# lazurite_rev3_3.net
KiCad netlist of a schematic drawn in EAGLE
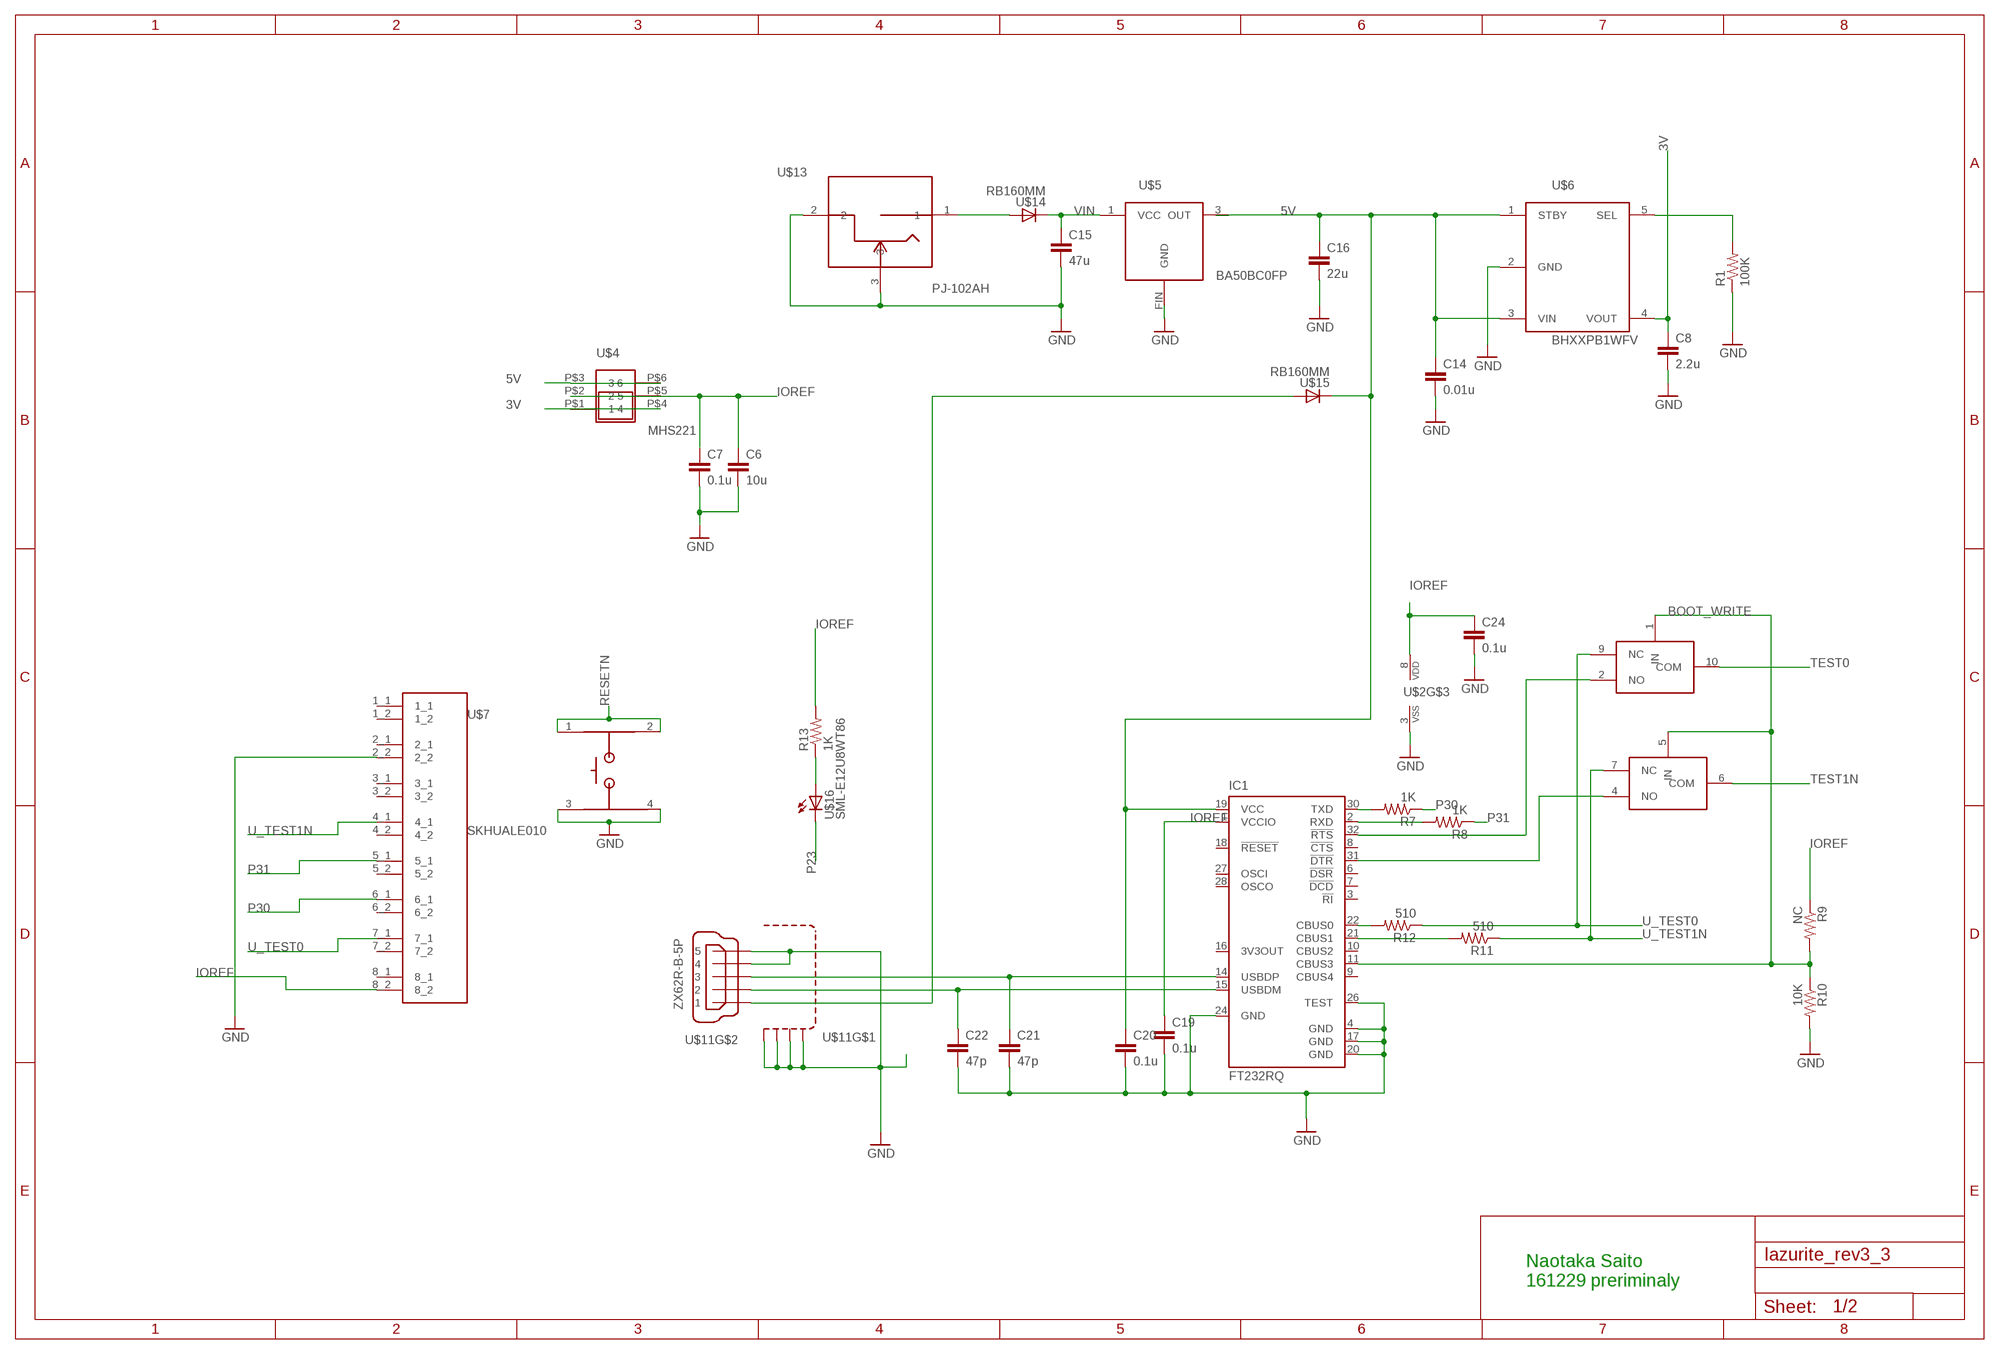
[diagram p0: schematic, sheet 1]
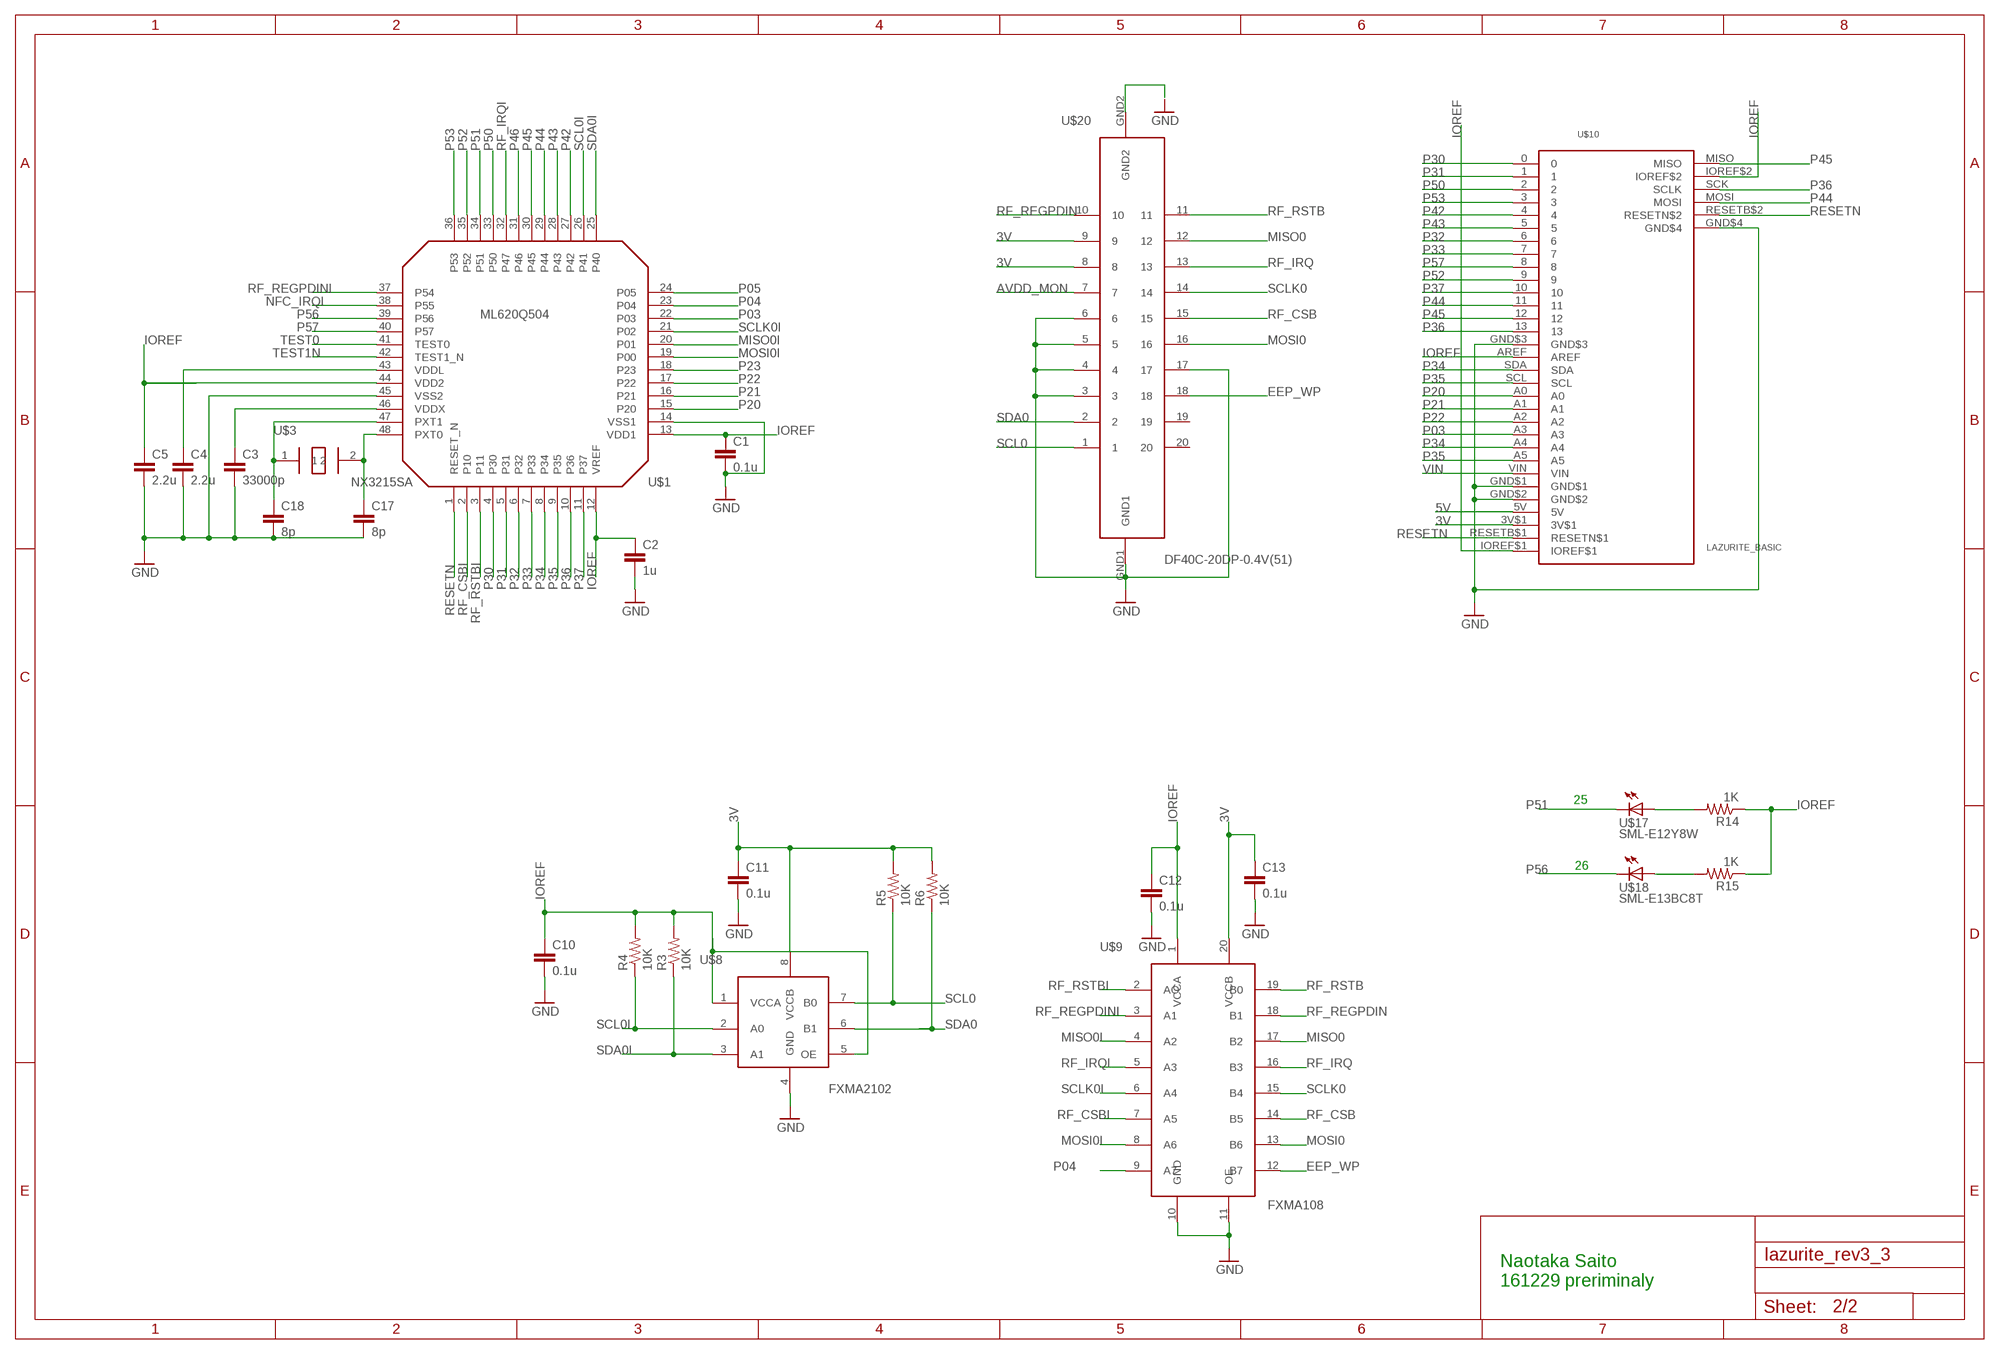
[diagram p1: schematic, sheet 2]

(export (version "E")
  (design (tool "Eeschema 10.0.6"))
  (components
    (comp (ref "C6")
      (value "10u")
      (footprint "eagle-import:C0402")
      (libsource (lib "eagle-import") (part "C-EUC0402"))
    )
    (comp (ref "C7")
      (value "0.1u")
      (footprint "eagle-import:C0402")
      (libsource (lib "eagle-import") (part "C-EUC0402"))
    )
    (comp (ref "C8")
      (value "2.2u")
      (footprint "eagle-import:C0402")
      (libsource (lib "eagle-import") (part "C-EUC0402"))
    )
    (comp (ref "C14")
      (value "0.01u")
      (footprint "eagle-import:C0402")
      (libsource (lib "eagle-import") (part "C-EUC0402"))
    )
    (comp (ref "C15")
      (value "47u")
      (footprint "eagle-import:C1210")
      (libsource (lib "eagle-import") (part "C-EUC1210"))
    )
    (comp (ref "C16")
      (value "22u")
      (footprint "eagle-import:C1206")
      (libsource (lib "eagle-import") (part "C-EUC1206"))
    )
    (comp (ref "C19")
      (value "0.1u")
      (footprint "eagle-import:C0402")
      (libsource (lib "eagle-import") (part "C-EUC0402"))
    )
    (comp (ref "C20")
      (value "0.1u")
      (footprint "eagle-import:C0402")
      (libsource (lib "eagle-import") (part "C-EUC0402"))
    )
    (comp (ref "C21")
      (value "47p")
      (footprint "eagle-import:C0402")
      (libsource (lib "eagle-import") (part "C-EUC0402"))
    )
    (comp (ref "C22")
      (value "47p")
      (footprint "eagle-import:C0402")
      (libsource (lib "eagle-import") (part "C-EUC0402"))
    )
    (comp (ref "C24")
      (value "0.1u")
      (footprint "eagle-import:C0402")
      (libsource (lib "eagle-import") (part "C-EUC0402"))
    )
    (comp (ref "IC1")
      (value "FT232RQ")
      (footprint "eagle-import:QFN32")
      (libsource (lib "eagle-import") (part "FT232RQ"))
    )
    (comp (ref "R1")
      (value "100K")
      (footprint "eagle-import:R0402")
      (libsource (lib "eagle-import") (part "R-US_R0402"))
    )
    (comp (ref "R7")
      (value "1K")
      (footprint "eagle-import:R0402")
      (libsource (lib "eagle-import") (part "R-US_R0402"))
    )
    (comp (ref "R8")
      (value "1K")
      (footprint "eagle-import:R0402")
      (libsource (lib "eagle-import") (part "R-US_R0402"))
    )
    (comp (ref "R9")
      (value "NC")
      (footprint "eagle-import:R0402")
      (libsource (lib "eagle-import") (part "R-US_R0402"))
    )
    (comp (ref "R10")
      (value "10K")
      (footprint "eagle-import:R0402")
      (libsource (lib "eagle-import") (part "R-US_R0402"))
    )
    (comp (ref "R11")
      (value "510")
      (footprint "eagle-import:R0402")
      (libsource (lib "eagle-import") (part "R-US_R0402"))
    )
    (comp (ref "R12")
      (value "510")
      (footprint "eagle-import:R0402")
      (libsource (lib "eagle-import") (part "R-US_R0402"))
    )
    (comp (ref "R13")
      (value "1K")
      (footprint "eagle-import:R0402")
      (libsource (lib "eagle-import") (part "R-US_R0402"))
    )
    (comp (ref "U$2")
      (value "TI-TS5A23159")
      (footprint "eagle-import:UQFN10")
      (libsource (lib "eagle-import") (part "TI-TS5A23159"))
    )
    (comp (ref "U$4")
      (value "MHS221")
      (footprint "eagle-import:MHS221")
      (libsource (lib "eagle-import") (part "MHS221"))
    )
    (comp (ref "U$5")
      (value "BA50BC0FP")
      (footprint "eagle-import:TO252-3")
      (libsource (lib "eagle-import") (part "BA50BC0FP"))
    )
    (comp (ref "U$6")
      (value "BHXXPB1WFV")
      (footprint "eagle-import:HVSOF5")
      (libsource (lib "eagle-import") (part "BHXXPB1WFV"))
    )
    (comp (ref "U$7")
      (value "SKHUALE010")
      (footprint "eagle-import:SKHUALE010")
      (libsource (lib "eagle-import") (part "SKHUALE010"))
    )
    (comp (ref "U$11")
      (value "ZX62R-B-5P")
      (footprint "eagle-import:ZX62R-B-5P")
      (libsource (lib "eagle-import") (part "MICRO-USB-SHIELD-ZX62R-B-5P"))
    )
    (comp (ref "U$12")
      (value "XB-1-X")
      (footprint "eagle-import:XB-1-X")
      (libsource (lib "eagle-import") (part "XB-1-X"))
    )
    (comp (ref "U$13")
      (value "PJ-102AH")
      (footprint "eagle-import:PJ-102H")
      (libsource (lib "eagle-import") (part "PJ-102AH"))
    )
    (comp (ref "U$14")
      (value "RB160MM")
      (footprint "eagle-import:RB160MM-30")
      (libsource (lib "eagle-import") (part "RB160MM"))
    )
    (comp (ref "U$15")
      (value "RB160MM")
      (footprint "eagle-import:RB160MM-30")
      (libsource (lib "eagle-import") (part "RB160MM"))
    )
    (comp (ref "U$16")
      (value "SML-E12U8WT86")
      (footprint "eagle-import:SML-E1X")
      (libsource (lib "eagle-import") (part "SML-E1X"))
    )
    (comp (ref "C1")
      (value "0.1u")
      (footprint "eagle-import:C0402")
      (libsource (lib "eagle-import") (part "C-EUC0402"))
    )
    (comp (ref "C2")
      (value "1u")
      (footprint "eagle-import:C0402")
      (libsource (lib "eagle-import") (part "C-EUC0402"))
    )
    (comp (ref "C3")
      (value "33000p")
      (footprint "eagle-import:C0402")
      (libsource (lib "eagle-import") (part "C-EUC0402"))
    )
    (comp (ref "C4")
      (value "2.2u")
      (footprint "eagle-import:C0402")
      (libsource (lib "eagle-import") (part "C-EUC0402"))
    )
    (comp (ref "C5")
      (value "2.2u")
      (footprint "eagle-import:C0402")
      (libsource (lib "eagle-import") (part "C-EUC0402"))
    )
    (comp (ref "C10")
      (value "0.1u")
      (footprint "eagle-import:C0402")
      (libsource (lib "eagle-import") (part "C-EUC0402"))
    )
    (comp (ref "C11")
      (value "0.1u")
      (footprint "eagle-import:C0402")
      (libsource (lib "eagle-import") (part "C-EUC0402"))
    )
    (comp (ref "C12")
      (value "0.1u")
      (footprint "eagle-import:C0402")
      (libsource (lib "eagle-import") (part "C-EUC0402"))
    )
    (comp (ref "C13")
      (value "0.1u")
      (footprint "eagle-import:C0402")
      (libsource (lib "eagle-import") (part "C-EUC0402"))
    )
    (comp (ref "C17")
      (value "8p")
      (footprint "eagle-import:C0402")
      (libsource (lib "eagle-import") (part "C-EUC0402"))
    )
    (comp (ref "C18")
      (value "8p")
      (footprint "eagle-import:C0402")
      (libsource (lib "eagle-import") (part "C-EUC0402"))
    )
    (comp (ref "R3")
      (value "10K")
      (footprint "eagle-import:R0402")
      (libsource (lib "eagle-import") (part "R-US_R0402"))
    )
    (comp (ref "R4")
      (value "10K")
      (footprint "eagle-import:R0402")
      (libsource (lib "eagle-import") (part "R-US_R0402"))
    )
    (comp (ref "R5")
      (value "10K")
      (footprint "eagle-import:R0402")
      (libsource (lib "eagle-import") (part "R-US_R0402"))
    )
    (comp (ref "R6")
      (value "10K")
      (footprint "eagle-import:R0402")
      (libsource (lib "eagle-import") (part "R-US_R0402"))
    )
    (comp (ref "R14")
      (value "1K")
      (footprint "eagle-import:R0402")
      (libsource (lib "eagle-import") (part "R-US_R0402"))
    )
    (comp (ref "R15")
      (value "1K")
      (footprint "eagle-import:R0402")
      (libsource (lib "eagle-import") (part "R-US_R0402"))
    )
    (comp (ref "U$1")
      (value "ML620Q504")
      (footprint "eagle-import:ML620Q504")
      (libsource (lib "eagle-import") (part "ML620Q504"))
    )
    (comp (ref "U$3")
      (value "NX3215SA")
      (footprint "eagle-import:NX3215SA-32,768K-SFD-MUA-14")
      (libsource (lib "eagle-import") (part "NX3215SA"))
    )
    (comp (ref "U$8")
      (value "FXMA2102")
      (footprint "eagle-import:MICROPACK")
      (libsource (lib "eagle-import") (part "FXMA2102"))
    )
    (comp (ref "U$9")
      (value "FXMA108")
      (footprint "eagle-import:FXMA108")
      (libsource (lib "eagle-import") (part "FXMA108"))
    )
    (comp (ref "U$10")
      (value "LAZURITE_BASIC")
      (footprint "eagle-import:LAZURITE_BASIC")
      (libsource (lib "eagle-import") (part "LAZURITE_BASIC"))
    )
    (comp (ref "U$17")
      (value "SML-E12Y8W")
      (footprint "eagle-import:SML-E1X")
      (libsource (lib "eagle-import") (part "SML-E1X"))
    )
    (comp (ref "U$18")
      (value "SML-E13BC8T")
      (footprint "eagle-import:SML-E1X")
      (libsource (lib "eagle-import") (part "SML-E1X"))
    )
    (comp (ref "U$20")
      (value "DF40C-20DP-0.4V(51)")
      (footprint "eagle-import:BP3596A")
      (libsource (lib "eagle-import") (part "BP3596A"))
    )
  )
  (nets
    (net (code "1") (name "3V") (class "Default")
      (node (ref "C11") (pin "1") (pinfunction "1_1") (pintype "passive"))
      (node (ref "C13") (pin "1") (pinfunction "1_1") (pintype "passive"))
      (node (ref "C8") (pin "1") (pinfunction "1_1") (pintype "passive"))
      (node (ref "R5") (pin "2") (pinfunction "2_2") (pintype "passive"))
      (node (ref "R6") (pin "2") (pinfunction "2_2") (pintype "passive"))
      (node (ref "U$10") (pin "3V$1") (pinfunction "3V$1_3V$1") (pintype "power_in"))
      (node (ref "U$20") (pin "8") (pinfunction "8_8") (pintype "bidirectional"))
      (node (ref "U$20") (pin "9") (pinfunction "9_9") (pintype "bidirectional"))
      (node (ref "U$4") (pin "P$1") (pinfunction "1_P$1") (pintype "bidirectional"))
      (node (ref "U$4") (pin "P$4") (pinfunction "4_P$4") (pintype "bidirectional"))
      (node (ref "U$6") (pin "4") (pinfunction "VOUT_4") (pintype "bidirectional"))
      (node (ref "U$8") (pin "8") (pinfunction "VCCB_8") (pintype "bidirectional"))
      (node (ref "U$9") (pin "20") (pinfunction "VCCB_20") (pintype "bidirectional"))
    )
    (net (code "2") (name "5V") (class "Default")
      (node (ref "C14") (pin "1") (pinfunction "1_1") (pintype "passive"))
      (node (ref "C16") (pin "1") (pinfunction "1_1") (pintype "passive"))
      (node (ref "C20") (pin "1") (pinfunction "1_1") (pintype "passive"))
      (node (ref "IC1") (pin "19") (pinfunction "VCC_19") (pintype "power_in"))
      (node (ref "U$10") (pin "5V") (pinfunction "5V_5V") (pintype "power_in"))
      (node (ref "U$15") (pin "C") (pinfunction "C_C") (pintype "passive"))
      (node (ref "U$4") (pin "P$3") (pinfunction "3_P$3") (pintype "bidirectional"))
      (node (ref "U$4") (pin "P$6") (pinfunction "6_P$6") (pintype "bidirectional"))
      (node (ref "U$5") (pin "3") (pinfunction "OUT_3") (pintype "bidirectional"))
      (node (ref "U$6") (pin "1") (pinfunction "STBY_1") (pintype "bidirectional"))
      (node (ref "U$6") (pin "3") (pinfunction "VIN_3") (pintype "bidirectional"))
    )
    (net (code "3") (name "AVDD_MON") (class "Default")
      (node (ref "U$20") (pin "7") (pinfunction "7_7") (pintype "bidirectional"))
    )
    (net (code "4") (name "BOOT_WRITE") (class "Default")
      (node (ref "IC1") (pin "11") (pinfunction "CBUS3_11") (pintype "bidirectional"))
      (node (ref "R10") (pin "1") (pinfunction "1_1") (pintype "passive"))
      (node (ref "R9") (pin "2") (pinfunction "2_2") (pintype "passive"))
      (node (ref "U$2") (pin "1") (pinfunction "IN_1") (pintype "bidirectional"))
      (node (ref "U$2") (pin "5") (pinfunction "IN_5") (pintype "bidirectional"))
    )
    (net (code "5") (name "EEP_WP") (class "Default")
      (node (ref "U$20") (pin "18") (pinfunction "18_18") (pintype "bidirectional"))
      (node (ref "U$9") (pin "12") (pinfunction "B7_12") (pintype "bidirectional"))
    )
    (net (code "6") (name "GND") (class "Default")
      (node (ref "C1") (pin "2") (pinfunction "2_2") (pintype "passive"))
      (node (ref "C10") (pin "2") (pinfunction "2_2") (pintype "passive"))
      (node (ref "C11") (pin "2") (pinfunction "2_2") (pintype "passive"))
      (node (ref "C12") (pin "2") (pinfunction "2_2") (pintype "passive"))
      (node (ref "C13") (pin "2") (pinfunction "2_2") (pintype "passive"))
      (node (ref "C14") (pin "2") (pinfunction "2_2") (pintype "passive"))
      (node (ref "C15") (pin "2") (pinfunction "2_2") (pintype "passive"))
      (node (ref "C16") (pin "2") (pinfunction "2_2") (pintype "passive"))
      (node (ref "C17") (pin "2") (pinfunction "2_2") (pintype "passive"))
      (node (ref "C18") (pin "2") (pinfunction "2_2") (pintype "passive"))
      (node (ref "C19") (pin "2") (pinfunction "2_2") (pintype "passive"))
      (node (ref "C2") (pin "2") (pinfunction "2_2") (pintype "passive"))
      (node (ref "C20") (pin "2") (pinfunction "2_2") (pintype "passive"))
      (node (ref "C21") (pin "2") (pinfunction "2_2") (pintype "passive"))
      (node (ref "C22") (pin "2") (pinfunction "2_2") (pintype "passive"))
      (node (ref "C24") (pin "2") (pinfunction "2_2") (pintype "passive"))
      (node (ref "C3") (pin "2") (pinfunction "2_2") (pintype "passive"))
      (node (ref "C4") (pin "2") (pinfunction "2_2") (pintype "passive"))
      (node (ref "C5") (pin "2") (pinfunction "2_2") (pintype "passive"))
      (node (ref "C6") (pin "2") (pinfunction "2_2") (pintype "passive"))
      (node (ref "C7") (pin "2") (pinfunction "2_2") (pintype "passive"))
      (node (ref "C8") (pin "2") (pinfunction "2_2") (pintype "passive"))
      (node (ref "IC1") (pin "17") (pinfunction "GND_17") (pintype "power_in"))
      (node (ref "IC1") (pin "20") (pinfunction "GND_20") (pintype "power_in"))
      (node (ref "IC1") (pin "24") (pinfunction "GND_24") (pintype "power_in"))
      (node (ref "IC1") (pin "26") (pinfunction "TEST_26") (pintype "input"))
      (node (ref "IC1") (pin "4") (pinfunction "GND_4") (pintype "power_in"))
      (node (ref "R1") (pin "1") (pinfunction "1_1") (pintype "passive"))
      (node (ref "R10") (pin "2") (pinfunction "2_2") (pintype "passive"))
      (node (ref "U$1") (pin "14") (pinfunction "VSS1_14") (pintype "bidirectional"))
      (node (ref "U$1") (pin "45") (pinfunction "VSS2_45") (pintype "bidirectional"))
      (node (ref "U$10") (pin "GND$1") (pinfunction "GND$1_GND$1") (pintype "power_in"))
      (node (ref "U$10") (pin "GND$2") (pinfunction "GND$2_GND$2") (pintype "power_in"))
      (node (ref "U$10") (pin "GND$3") (pinfunction "GND$3_GND$3") (pintype "power_in"))
      (node (ref "U$10") (pin "GND$4") (pinfunction "GND$4_GND$4") (pintype "power_in"))
      (node (ref "U$11") (pin "4") (pinfunction "4_4") (pintype "input"))
      (node (ref "U$11") (pin "5") (pinfunction "5_5") (pintype "input"))
      (node (ref "U$11") (pin "M1") (pinfunction "S1_M1") (pintype "passive"))
      (node (ref "U$11") (pin "M2") (pinfunction "S2_M2") (pintype "passive"))
      (node (ref "U$11") (pin "M3") (pinfunction "S3_M3") (pintype "passive"))
      (node (ref "U$11") (pin "M4") (pinfunction "S4_M4") (pintype "passive"))
      (node (ref "U$12") (pin "2_2") (pinfunction "2_2_2_2") (pintype "bidirectional"))
      (node (ref "U$13") (pin "2") (pinfunction "2_2") (pintype "bidirectional"))
      (node (ref "U$13") (pin "3") (pinfunction "3_3") (pintype "bidirectional"))
      (node (ref "U$2") (pin "3") (pinfunction "VSS_3") (pintype "power_in"))
      (node (ref "U$20") (pin "17") (pinfunction "17_17") (pintype "bidirectional"))
      (node (ref "U$20") (pin "3") (pinfunction "3_3") (pintype "bidirectional"))
      (node (ref "U$20") (pin "4") (pinfunction "4_4") (pintype "bidirectional"))
      (node (ref "U$20") (pin "5") (pinfunction "5_5") (pintype "bidirectional"))
      (node (ref "U$20") (pin "6") (pinfunction "6_6") (pintype "bidirectional"))
      (node (ref "U$20") (pin "GND1") (pinfunction "GND1_GND1") (pintype "bidirectional"))
      (node (ref "U$5") (pin "FIN") (pinfunction "GND_FIN") (pintype "bidirectional"))
      (node (ref "U$6") (pin "2") (pinfunction "GND_2") (pintype "bidirectional"))
      (node (ref "U$7") (pin "3") (pinfunction "3_3") (pintype "bidirectional"))
      (node (ref "U$7") (pin "4") (pinfunction "4_4") (pintype "bidirectional"))
      (node (ref "U$8") (pin "4") (pinfunction "GND_4") (pintype "bidirectional"))
      (node (ref "U$9") (pin "10") (pinfunction "GND_10") (pintype "bidirectional"))
      (node (ref "U$9") (pin "11") (pinfunction "OE_11") (pintype "bidirectional"))
    )
    (net (code "7") (name "IOREF") (class "Default")
      (node (ref "C1") (pin "1") (pinfunction "1_1") (pintype "passive"))
      (node (ref "C10") (pin "1") (pinfunction "1_1") (pintype "passive"))
      (node (ref "C12") (pin "1") (pinfunction "1_1") (pintype "passive"))
      (node (ref "C19") (pin "1") (pinfunction "1_1") (pintype "passive"))
      (node (ref "C2") (pin "1") (pinfunction "1_1") (pintype "passive"))
      (node (ref "C24") (pin "1") (pinfunction "1_1") (pintype "passive"))
      (node (ref "C5") (pin "1") (pinfunction "1_1") (pintype "passive"))
      (node (ref "C6") (pin "1") (pinfunction "1_1") (pintype "passive"))
      (node (ref "C7") (pin "1") (pinfunction "1_1") (pintype "passive"))
      (node (ref "IC1") (pin "1") (pinfunction "VCCIO_1") (pintype "power_in"))
      (node (ref "R13") (pin "2") (pinfunction "2_2") (pintype "passive"))
      (node (ref "R14") (pin "1") (pinfunction "1_1") (pintype "passive"))
      (node (ref "R15") (pin "1") (pinfunction "1_1") (pintype "passive"))
      (node (ref "R3") (pin "2") (pinfunction "2_2") (pintype "passive"))
      (node (ref "R4") (pin "2") (pinfunction "2_2") (pintype "passive"))
      (node (ref "R9") (pin "1") (pinfunction "1_1") (pintype "passive"))
      (node (ref "U$1") (pin "12") (pinfunction "VREF_12") (pintype "bidirectional"))
      (node (ref "U$1") (pin "13") (pinfunction "VDD1_13") (pintype "bidirectional"))
      (node (ref "U$1") (pin "44") (pinfunction "VDD2_44") (pintype "bidirectional"))
      (node (ref "U$10") (pin "AREF") (pinfunction "AREF_AREF") (pintype "power_in"))
      (node (ref "U$10") (pin "IOREF$1") (pinfunction "IOREF$1_IOREF$1") (pintype "bidirectional"))
      (node (ref "U$10") (pin "IOREF$2") (pinfunction "IOREF$2_IOREF$2") (pintype "power_in"))
      (node (ref "U$12") (pin "8_2") (pinfunction "8_2_8_2") (pintype "bidirectional"))
      (node (ref "U$2") (pin "8") (pinfunction "VDD_8") (pintype "power_in"))
      (node (ref "U$4") (pin "P$2") (pinfunction "2_P$2") (pintype "bidirectional"))
      (node (ref "U$4") (pin "P$5") (pinfunction "5_P$5") (pintype "bidirectional"))
      (node (ref "U$8") (pin "1") (pinfunction "VCCA_1") (pintype "bidirectional"))
      (node (ref "U$8") (pin "5") (pinfunction "OE_5") (pintype "bidirectional"))
      (node (ref "U$9") (pin "1") (pinfunction "VCCA_1") (pintype "bidirectional"))
    )
    (net (code "8") (name "MISO0") (class "Default")
      (node (ref "U$20") (pin "12") (pinfunction "12_12") (pintype "bidirectional"))
      (node (ref "U$9") (pin "17") (pinfunction "B2_17") (pintype "bidirectional"))
    )
    (net (code "9") (name "MISO0I") (class "Default")
      (node (ref "U$1") (pin "20") (pinfunction "P01_20") (pintype "bidirectional"))
      (node (ref "U$9") (pin "4") (pinfunction "A2_4") (pintype "bidirectional"))
    )
    (net (code "10") (name "MOSI0") (class "Default")
      (node (ref "U$20") (pin "16") (pinfunction "16_16") (pintype "bidirectional"))
      (node (ref "U$9") (pin "13") (pinfunction "B6_13") (pintype "bidirectional"))
    )
    (net (code "11") (name "MOSI0I") (class "Default")
      (node (ref "U$1") (pin "19") (pinfunction "P00_19") (pintype "bidirectional"))
      (node (ref "U$9") (pin "8") (pinfunction "A6_8") (pintype "bidirectional"))
    )
    (net (code "12") (name "NFC_IRQI") (class "Default")
      (node (ref "U$1") (pin "38") (pinfunction "P55_38") (pintype "bidirectional"))
    )
    (net (code "13") (name "Net-(IC1-CBUS0)") (class "Default")
      (node (ref "IC1") (pin "22") (pinfunction "CBUS0_22") (pintype "bidirectional"))
      (node (ref "R12") (pin "2") (pinfunction "2_2") (pintype "passive"))
    )
    (net (code "14") (name "Net-(IC1-CBUS1)") (class "Default")
      (node (ref "IC1") (pin "21") (pinfunction "CBUS1_21") (pintype "bidirectional"))
      (node (ref "R11") (pin "2") (pinfunction "2_2") (pintype "passive"))
    )
    (net (code "15") (name "Net-(IC1-RXD)") (class "Default")
      (node (ref "IC1") (pin "2") (pinfunction "RXD_2") (pintype "input"))
      (node (ref "R8") (pin "2") (pinfunction "2_2") (pintype "passive"))
    )
    (net (code "16") (name "Net-(IC1-TXD)") (class "Default")
      (node (ref "IC1") (pin "30") (pinfunction "TXD_30") (pintype "output"))
      (node (ref "R7") (pin "2") (pinfunction "2_2") (pintype "passive"))
    )
    (net (code "17") (name "Net-(IC1-USBDM)") (class "Default")
      (node (ref "C22") (pin "1") (pinfunction "1_1") (pintype "passive"))
      (node (ref "IC1") (pin "15") (pinfunction "USBDM_15") (pintype "bidirectional"))
      (node (ref "U$11") (pin "2") (pinfunction "2_2") (pintype "input"))
    )
    (net (code "18") (name "Net-(IC1-USBDP)") (class "Default")
      (node (ref "C21") (pin "1") (pinfunction "1_1") (pintype "passive"))
      (node (ref "IC1") (pin "14") (pinfunction "USBDP_14") (pintype "bidirectional"))
      (node (ref "U$11") (pin "3") (pinfunction "3_3") (pintype "input"))
    )
    (net (code "19") (name "Net-(IC1-~{DTR})") (class "Default")
      (node (ref "IC1") (pin "31") (pinfunction "~{DTR}_31") (pintype "output"))
      (node (ref "U$2") (pin "4") (pinfunction "NO_4") (pintype "bidirectional"))
    )
    (net (code "20") (name "Net-(IC1-~{RTS})") (class "Default")
      (node (ref "IC1") (pin "32") (pinfunction "~{RTS}_32") (pintype "output"))
      (node (ref "U$2") (pin "2") (pinfunction "NO_2") (pintype "bidirectional"))
    )
    (net (code "21") (name "Net-(R13-Pad1)") (class "Default")
      (node (ref "R13") (pin "1") (pinfunction "1_1") (pintype "passive"))
      (node (ref "U$16") (pin "A") (pinfunction "A_A") (pintype "passive"))
    )
    (net (code "22") (name "Net-(R14-Pad2)") (class "Default")
      (node (ref "R14") (pin "2") (pinfunction "2_2") (pintype "passive"))
      (node (ref "U$17") (pin "A") (pinfunction "A_A") (pintype "passive"))
    )
    (net (code "23") (name "Net-(R15-Pad2)") (class "Default")
      (node (ref "R15") (pin "2") (pinfunction "2_2") (pintype "passive"))
      (node (ref "U$18") (pin "A") (pinfunction "A_A") (pintype "passive"))
    )
    (net (code "24") (name "Net-(U$1-PXT0)") (class "Default")
      (node (ref "C17") (pin "1") (pinfunction "1_1") (pintype "passive"))
      (node (ref "U$1") (pin "48") (pinfunction "PXT0_48") (pintype "bidirectional"))
      (node (ref "U$3") (pin "2") (pinfunction "2_2") (pintype "bidirectional"))
    )
    (net (code "25") (name "Net-(U$1-PXT1)") (class "Default")
      (node (ref "C18") (pin "1") (pinfunction "1_1") (pintype "passive"))
      (node (ref "U$1") (pin "47") (pinfunction "PXT1_47") (pintype "bidirectional"))
      (node (ref "U$3") (pin "1") (pinfunction "1_1") (pintype "bidirectional"))
    )
    (net (code "26") (name "Net-(U$1-VDDL)") (class "Default")
      (node (ref "C4") (pin "1") (pinfunction "1_1") (pintype "passive"))
      (node (ref "U$1") (pin "43") (pinfunction "VDDL_43") (pintype "bidirectional"))
    )
    (net (code "27") (name "Net-(U$1-VDDX)") (class "Default")
      (node (ref "C3") (pin "1") (pinfunction "1_1") (pintype "passive"))
      (node (ref "U$1") (pin "46") (pinfunction "VDDX_46") (pintype "bidirectional"))
    )
    (net (code "28") (name "Net-(U$6-SEL)") (class "Default")
      (node (ref "R1") (pin "2") (pinfunction "2_2") (pintype "passive"))
      (node (ref "U$6") (pin "5") (pinfunction "SEL_5") (pintype "bidirectional"))
    )
    (net (code "29") (name "Net-(U$11-Pad1)") (class "Default")
      (node (ref "U$11") (pin "1") (pinfunction "1_1") (pintype "input"))
      (node (ref "U$15") (pin "A") (pinfunction "A_A") (pintype "passive"))
    )
    (net (code "30") (name "Net-(U$13-Pad1)") (class "Default")
      (node (ref "U$13") (pin "1") (pinfunction "1_1") (pintype "bidirectional"))
      (node (ref "U$14") (pin "A") (pinfunction "A_A") (pintype "passive"))
    )
    (net (code "31") (name "P03") (class "Default")
      (node (ref "U$1") (pin "22") (pinfunction "P03_22") (pintype "bidirectional"))
      (node (ref "U$10") (pin "A3") (pinfunction "A3_A3") (pintype "bidirectional"))
    )
    (net (code "32") (name "P04") (class "Default")
      (node (ref "U$1") (pin "23") (pinfunction "P04_23") (pintype "bidirectional"))
      (node (ref "U$9") (pin "9") (pinfunction "A7_9") (pintype "bidirectional"))
    )
    (net (code "33") (name "P05") (class "Default")
      (node (ref "U$1") (pin "24") (pinfunction "P05_24") (pintype "bidirectional"))
    )
    (net (code "34") (name "P20") (class "Default")
      (node (ref "U$1") (pin "15") (pinfunction "P20_15") (pintype "bidirectional"))
      (node (ref "U$10") (pin "A0") (pinfunction "A0_A0") (pintype "bidirectional"))
    )
    (net (code "35") (name "P21") (class "Default")
      (node (ref "U$1") (pin "16") (pinfunction "P21_16") (pintype "bidirectional"))
      (node (ref "U$10") (pin "A1") (pinfunction "A1_A1") (pintype "bidirectional"))
    )
    (net (code "36") (name "P22") (class "Default")
      (node (ref "U$1") (pin "17") (pinfunction "P22_17") (pintype "bidirectional"))
      (node (ref "U$10") (pin "A2") (pinfunction "A2_A2") (pintype "bidirectional"))
    )
    (net (code "37") (name "P23") (class "Default")
      (node (ref "U$1") (pin "18") (pinfunction "P23_18") (pintype "bidirectional"))
      (node (ref "U$16") (pin "C") (pinfunction "C_C") (pintype "passive"))
    )
    (net (code "38") (name "P30") (class "Default")
      (node (ref "R7") (pin "1") (pinfunction "1_1") (pintype "passive"))
      (node (ref "U$1") (pin "4") (pinfunction "P30_4") (pintype "bidirectional"))
      (node (ref "U$10") (pin "0") (pinfunction "0_0") (pintype "bidirectional"))
      (node (ref "U$12") (pin "6_1") (pinfunction "6_1_6_1") (pintype "bidirectional"))
    )
    (net (code "39") (name "P31") (class "Default")
      (node (ref "R8") (pin "1") (pinfunction "1_1") (pintype "passive"))
      (node (ref "U$1") (pin "5") (pinfunction "P31_5") (pintype "bidirectional"))
      (node (ref "U$10") (pin "1") (pinfunction "1_1") (pintype "bidirectional"))
      (node (ref "U$12") (pin "5_1") (pinfunction "5_1_5_1") (pintype "bidirectional"))
    )
    (net (code "40") (name "P32") (class "Default")
      (node (ref "U$1") (pin "6") (pinfunction "P32_6") (pintype "bidirectional"))
      (node (ref "U$10") (pin "6") (pinfunction "6_6") (pintype "bidirectional"))
    )
    (net (code "41") (name "P33") (class "Default")
      (node (ref "U$1") (pin "7") (pinfunction "P33_7") (pintype "bidirectional"))
      (node (ref "U$10") (pin "7") (pinfunction "7_7") (pintype "bidirectional"))
    )
    (net (code "42") (name "P34") (class "Default")
      (node (ref "U$1") (pin "8") (pinfunction "P34_8") (pintype "bidirectional"))
      (node (ref "U$10") (pin "A4") (pinfunction "A4_A4") (pintype "bidirectional"))
      (node (ref "U$10") (pin "SDA") (pinfunction "SDA_SDA") (pintype "bidirectional"))
    )
    (net (code "43") (name "P35") (class "Default")
      (node (ref "U$1") (pin "9") (pinfunction "P35_9") (pintype "bidirectional"))
      (node (ref "U$10") (pin "A5") (pinfunction "A5_A5") (pintype "bidirectional"))
      (node (ref "U$10") (pin "SCL") (pinfunction "SCL_SCL") (pintype "bidirectional"))
    )
    (net (code "44") (name "P36") (class "Default")
      (node (ref "U$1") (pin "10") (pinfunction "P36_10") (pintype "bidirectional"))
      (node (ref "U$10") (pin "13") (pinfunction "13_13") (pintype "bidirectional"))
      (node (ref "U$10") (pin "SCK") (pinfunction "SCLK_SCK") (pintype "bidirectional"))
    )
    (net (code "45") (name "P37") (class "Default")
      (node (ref "U$1") (pin "11") (pinfunction "P37_11") (pintype "bidirectional"))
      (node (ref "U$10") (pin "10") (pinfunction "10_10") (pintype "bidirectional"))
    )
    (net (code "46") (name "P42") (class "Default")
      (node (ref "U$1") (pin "27") (pinfunction "P42_27") (pintype "bidirectional"))
      (node (ref "U$10") (pin "4") (pinfunction "4_4") (pintype "bidirectional"))
    )
    (net (code "47") (name "P43") (class "Default")
      (node (ref "U$1") (pin "28") (pinfunction "P43_28") (pintype "bidirectional"))
      (node (ref "U$10") (pin "5") (pinfunction "5_5") (pintype "bidirectional"))
    )
    (net (code "48") (name "P44") (class "Default")
      (node (ref "U$1") (pin "29") (pinfunction "P44_29") (pintype "bidirectional"))
      (node (ref "U$10") (pin "11") (pinfunction "11_11") (pintype "bidirectional"))
      (node (ref "U$10") (pin "MOSI") (pinfunction "MOSI_MOSI") (pintype "bidirectional"))
    )
    (net (code "49") (name "P45") (class "Default")
      (node (ref "U$1") (pin "30") (pinfunction "P45_30") (pintype "bidirectional"))
      (node (ref "U$10") (pin "12") (pinfunction "12_12") (pintype "bidirectional"))
      (node (ref "U$10") (pin "MISO") (pinfunction "MISO_MISO") (pintype "bidirectional"))
    )
    (net (code "50") (name "P46") (class "Default")
      (node (ref "U$1") (pin "31") (pinfunction "P46_31") (pintype "bidirectional"))
    )
    (net (code "51") (name "P50") (class "Default")
      (node (ref "U$1") (pin "33") (pinfunction "P50_33") (pintype "bidirectional"))
      (node (ref "U$10") (pin "2") (pinfunction "2_2") (pintype "bidirectional"))
    )
    (net (code "52") (name "P51") (class "Default")
      (node (ref "U$1") (pin "34") (pinfunction "P51_34") (pintype "bidirectional"))
      (node (ref "U$17") (pin "C") (pinfunction "C_C") (pintype "passive"))
    )
    (net (code "53") (name "P52") (class "Default")
      (node (ref "U$1") (pin "35") (pinfunction "P52_35") (pintype "bidirectional"))
      (node (ref "U$10") (pin "9") (pinfunction "9_9") (pintype "bidirectional"))
    )
    (net (code "54") (name "P53") (class "Default")
      (node (ref "U$1") (pin "36") (pinfunction "P53_36") (pintype "bidirectional"))
      (node (ref "U$10") (pin "3") (pinfunction "3_3") (pintype "bidirectional"))
    )
    (net (code "55") (name "P56") (class "Default")
      (node (ref "U$1") (pin "39") (pinfunction "P56_39") (pintype "bidirectional"))
      (node (ref "U$18") (pin "C") (pinfunction "C_C") (pintype "passive"))
    )
    (net (code "56") (name "P57") (class "Default")
      (node (ref "U$1") (pin "40") (pinfunction "P57_40") (pintype "bidirectional"))
      (node (ref "U$10") (pin "8") (pinfunction "8_8") (pintype "bidirectional"))
    )
    (net (code "57") (name "RESETN") (class "Default")
      (node (ref "U$1") (pin "1") (pinfunction "RESET_N_1") (pintype "bidirectional"))
      (node (ref "U$10") (pin "RESETB$1") (pinfunction "RESETN$1_RESETB$1") (pintype "bidirectional"))
      (node (ref "U$10") (pin "RESETB$2") (pinfunction "RESETN$2_RESETB$2") (pintype "bidirectional"))
      (node (ref "U$7") (pin "1") (pinfunction "1_1") (pintype "bidirectional"))
      (node (ref "U$7") (pin "2") (pinfunction "2_2") (pintype "bidirectional"))
    )
    (net (code "58") (name "RF_CSB") (class "Default")
      (node (ref "U$20") (pin "15") (pinfunction "15_15") (pintype "bidirectional"))
      (node (ref "U$9") (pin "14") (pinfunction "B5_14") (pintype "bidirectional"))
    )
    (net (code "59") (name "RF_CSBI") (class "Default")
      (node (ref "U$1") (pin "2") (pinfunction "P10_2") (pintype "bidirectional"))
      (node (ref "U$9") (pin "7") (pinfunction "A5_7") (pintype "bidirectional"))
    )
    (net (code "60") (name "RF_IRQ") (class "Default")
      (node (ref "U$20") (pin "13") (pinfunction "13_13") (pintype "bidirectional"))
      (node (ref "U$9") (pin "16") (pinfunction "B3_16") (pintype "bidirectional"))
    )
    (net (code "61") (name "RF_IRQI") (class "Default")
      (node (ref "U$1") (pin "32") (pinfunction "P47_32") (pintype "bidirectional"))
      (node (ref "U$9") (pin "5") (pinfunction "A3_5") (pintype "bidirectional"))
    )
    (net (code "62") (name "RF_REGPDIN") (class "Default")
      (node (ref "U$20") (pin "10") (pinfunction "10_10") (pintype "bidirectional"))
      (node (ref "U$9") (pin "18") (pinfunction "B1_18") (pintype "bidirectional"))
    )
    (net (code "63") (name "RF_REGPDINI") (class "Default")
      (node (ref "U$1") (pin "37") (pinfunction "P54_37") (pintype "bidirectional"))
      (node (ref "U$9") (pin "3") (pinfunction "A1_3") (pintype "bidirectional"))
    )
    (net (code "64") (name "RF_RSTB") (class "Default")
      (node (ref "U$20") (pin "11") (pinfunction "11_11") (pintype "bidirectional"))
      (node (ref "U$9") (pin "19") (pinfunction "B0_19") (pintype "bidirectional"))
    )
    (net (code "65") (name "RF_RSTBI") (class "Default")
      (node (ref "U$1") (pin "3") (pinfunction "P11_3") (pintype "bidirectional"))
      (node (ref "U$9") (pin "2") (pinfunction "AO_2") (pintype "bidirectional"))
    )
    (net (code "66") (name "SCL0") (class "Default")
      (node (ref "R5") (pin "1") (pinfunction "1_1") (pintype "passive"))
      (node (ref "U$20") (pin "1") (pinfunction "1_1") (pintype "bidirectional"))
      (node (ref "U$8") (pin "7") (pinfunction "B0_7") (pintype "bidirectional"))
    )
    (net (code "67") (name "SCL0I") (class "Default")
      (node (ref "R4") (pin "1") (pinfunction "1_1") (pintype "passive"))
      (node (ref "U$1") (pin "26") (pinfunction "P41_26") (pintype "bidirectional"))
      (node (ref "U$8") (pin "2") (pinfunction "A0_2") (pintype "bidirectional"))
    )
    (net (code "68") (name "SCLK0") (class "Default")
      (node (ref "U$20") (pin "14") (pinfunction "14_14") (pintype "bidirectional"))
      (node (ref "U$9") (pin "15") (pinfunction "B4_15") (pintype "bidirectional"))
    )
    (net (code "69") (name "SCLK0I") (class "Default")
      (node (ref "U$1") (pin "21") (pinfunction "P02_21") (pintype "bidirectional"))
      (node (ref "U$9") (pin "6") (pinfunction "A4_6") (pintype "bidirectional"))
    )
    (net (code "70") (name "SDA0") (class "Default")
      (node (ref "R6") (pin "1") (pinfunction "1_1") (pintype "passive"))
      (node (ref "U$20") (pin "2") (pinfunction "2_2") (pintype "bidirectional"))
      (node (ref "U$8") (pin "6") (pinfunction "B1_6") (pintype "bidirectional"))
    )
    (net (code "71") (name "SDA0I") (class "Default")
      (node (ref "R3") (pin "1") (pinfunction "1_1") (pintype "passive"))
      (node (ref "U$1") (pin "25") (pinfunction "P40_25") (pintype "bidirectional"))
      (node (ref "U$8") (pin "3") (pinfunction "A1_3") (pintype "bidirectional"))
    )
    (net (code "72") (name "TEST0") (class "Default")
      (node (ref "U$1") (pin "41") (pinfunction "TEST0_41") (pintype "bidirectional"))
      (node (ref "U$2") (pin "10") (pinfunction "COM_10") (pintype "bidirectional"))
    )
    (net (code "73") (name "TEST1N") (class "Default")
      (node (ref "U$1") (pin "42") (pinfunction "TEST1_N_42") (pintype "bidirectional"))
      (node (ref "U$2") (pin "6") (pinfunction "COM_6") (pintype "bidirectional"))
    )
    (net (code "74") (name "U_TEST0") (class "Default")
      (node (ref "R12") (pin "1") (pinfunction "1_1") (pintype "passive"))
      (node (ref "U$12") (pin "7_1") (pinfunction "7_1_7_1") (pintype "bidirectional"))
      (node (ref "U$2") (pin "9") (pinfunction "NC_9") (pintype "bidirectional"))
    )
    (net (code "75") (name "U_TEST1N") (class "Default")
      (node (ref "R11") (pin "1") (pinfunction "1_1") (pintype "passive"))
      (node (ref "U$12") (pin "4_1") (pinfunction "4_1_4_1") (pintype "bidirectional"))
      (node (ref "U$2") (pin "7") (pinfunction "NC_7") (pintype "bidirectional"))
    )
    (net (code "76") (name "VIN") (class "Default")
      (node (ref "C15") (pin "1") (pinfunction "1_1") (pintype "passive"))
      (node (ref "U$10") (pin "VIN") (pinfunction "VIN_VIN") (pintype "power_in"))
      (node (ref "U$14") (pin "C") (pinfunction "C_C") (pintype "passive"))
      (node (ref "U$5") (pin "1") (pinfunction "VCC_1") (pintype "bidirectional"))
    )
    (net (code "77") (name "unconnected-(IC1-3V3OUT-Pad16)") (class "Default")
      (node (ref "IC1") (pin "16") (pinfunction "3V3OUT_16") (pintype "output"))
    )
    (net (code "78") (name "unconnected-(IC1-CBUS2-Pad10)") (class "Default")
      (node (ref "IC1") (pin "10") (pinfunction "CBUS2_10") (pintype "bidirectional"))
    )
    (net (code "79") (name "unconnected-(IC1-CBUS4-Pad9)") (class "Default")
      (node (ref "IC1") (pin "9") (pinfunction "CBUS4_9") (pintype "bidirectional"))
    )
    (net (code "80") (name "unconnected-(IC1-OSCI-Pad27)") (class "Default")
      (node (ref "IC1") (pin "27") (pinfunction "OSCI_27") (pintype "input"))
    )
    (net (code "81") (name "unconnected-(IC1-OSCO-Pad28)") (class "Default")
      (node (ref "IC1") (pin "28") (pinfunction "OSCO_28") (pintype "output"))
    )
    (net (code "82") (name "unconnected-(IC1-~{CTS}-Pad8)") (class "Default")
      (node (ref "IC1") (pin "8") (pinfunction "~{CTS}_8") (pintype "input"))
    )
    (net (code "83") (name "unconnected-(IC1-~{DCD}-Pad7)") (class "Default")
      (node (ref "IC1") (pin "7") (pinfunction "~{DCD}_7") (pintype "input"))
    )
    (net (code "84") (name "unconnected-(IC1-~{DSR}-Pad6)") (class "Default")
      (node (ref "IC1") (pin "6") (pinfunction "~{DSR}_6") (pintype "input"))
    )
    (net (code "85") (name "unconnected-(IC1-~{RESET}-Pad18)") (class "Default")
      (node (ref "IC1") (pin "18") (pinfunction "~{RESET}_18") (pintype "input"))
    )
    (net (code "86") (name "unconnected-(IC1-~{RI}-Pad3)") (class "Default")
      (node (ref "IC1") (pin "3") (pinfunction "~{RI}_3") (pintype "input"))
    )
    (net (code "87") (name "unconnected-(U$12-Pad1_1)") (class "Default")
      (node (ref "U$12") (pin "1_1") (pinfunction "1_1_1_1") (pintype "bidirectional"))
    )
    (net (code "88") (name "unconnected-(U$12-Pad1_2)") (class "Default")
      (node (ref "U$12") (pin "1_2") (pinfunction "1_2_1_2") (pintype "bidirectional"))
    )
    (net (code "89") (name "unconnected-(U$12-Pad2_1)") (class "Default")
      (node (ref "U$12") (pin "2_1") (pinfunction "2_1_2_1") (pintype "bidirectional"))
    )
    (net (code "90") (name "unconnected-(U$12-Pad3_1)") (class "Default")
      (node (ref "U$12") (pin "3_1") (pinfunction "3_1_3_1") (pintype "bidirectional"))
    )
    (net (code "91") (name "unconnected-(U$12-Pad3_2)") (class "Default")
      (node (ref "U$12") (pin "3_2") (pinfunction "3_2_3_2") (pintype "bidirectional"))
    )
    (net (code "92") (name "unconnected-(U$12-Pad4_2)") (class "Default")
      (node (ref "U$12") (pin "4_2") (pinfunction "4_2_4_2") (pintype "bidirectional"))
    )
    (net (code "93") (name "unconnected-(U$12-Pad5_2)") (class "Default")
      (node (ref "U$12") (pin "5_2") (pinfunction "5_2_5_2") (pintype "bidirectional"))
    )
    (net (code "94") (name "unconnected-(U$12-Pad6_2)") (class "Default")
      (node (ref "U$12") (pin "6_2") (pinfunction "6_2_6_2") (pintype "bidirectional"))
    )
    (net (code "95") (name "unconnected-(U$12-Pad7_2)") (class "Default")
      (node (ref "U$12") (pin "7_2") (pinfunction "7_2_7_2") (pintype "bidirectional"))
    )
    (net (code "96") (name "unconnected-(U$12-Pad8_1)") (class "Default")
      (node (ref "U$12") (pin "8_1") (pinfunction "8_1_8_1") (pintype "bidirectional"))
    )
    (net (code "97") (name "unconnected-(U$20-Pad19)") (class "Default")
      (node (ref "U$20") (pin "19") (pinfunction "19_19") (pintype "bidirectional"))
    )
    (net (code "98") (name "unconnected-(U$20-Pad20)") (class "Default")
      (node (ref "U$20") (pin "20") (pinfunction "20_20") (pintype "bidirectional"))
    )
    (net (code "99") (name "unconnected-(U$20-PadGND2)") (class "Default")
      (node (ref "U$20") (pin "GND2") (pinfunction "GND2_GND2") (pintype "bidirectional"))
    )
  )
)
